# 93_HW_ID.net
KiCad netlist of a schematic drawn in Altium Designer
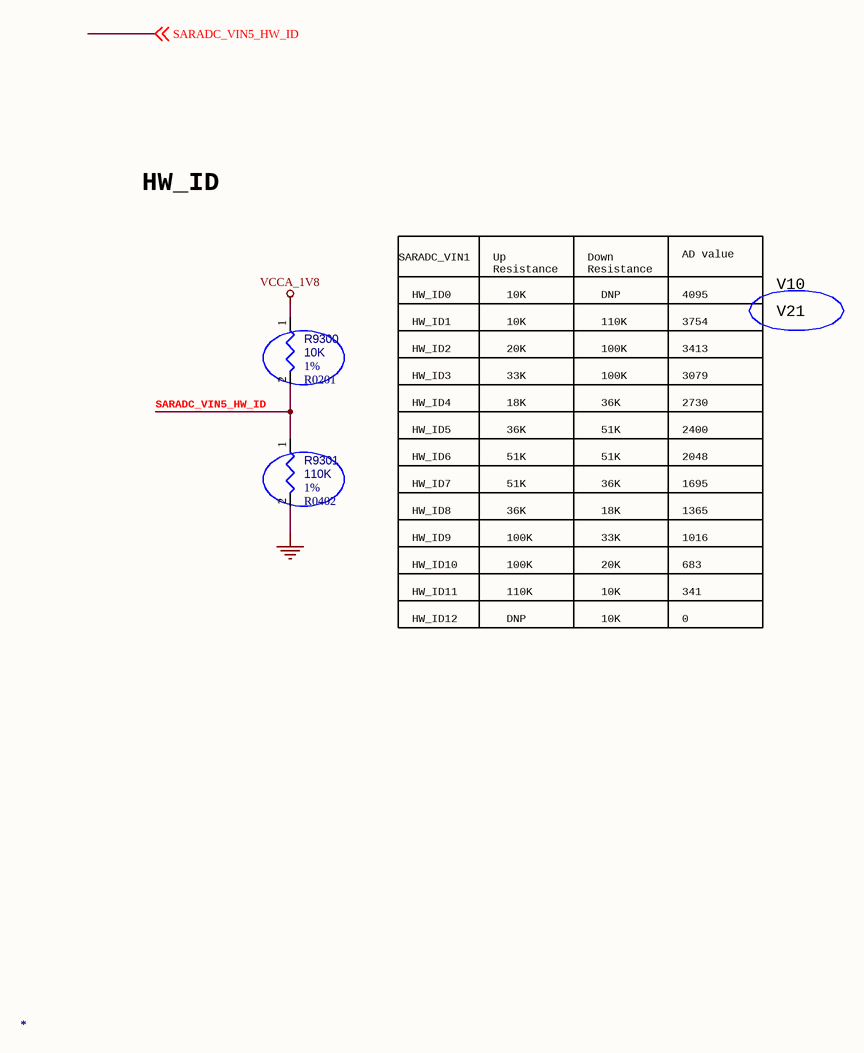
[diagram p0: 93.HW_ID.SchDoc]

(export (version "E")
  (design (tool "Eeschema 10.0.6"))
  (components
    (comp (ref "R9300")
      (value "*")
      (footprint "R0402")
      (description "НЁУГєсД¤µзЧи,10K,+/-1%,R0201,1/20W.")
      (fields
        (field (name "PCB FOOTPRINT") "R0201")
        (field (name "TOLERANCE") "1%")
        (field (name "MANUFACTURER") "YAGEO")
        (field (name "ALTIUM_UNNAMED_1") "10K")
        (field (name "CREATED BY") "YTL")
      )
      (libsource (lib "*") (part "RESISTOR_Dup1"))
    )
    (comp (ref "R9301")
      (value "*")
      (footprint "R0402")
      (description "НЁУГєсД¤µзЧи,110K,+/-1%,R0402,1/16W.")
      (fields
        (field (name "PCB FOOTPRINT") "R0402")
        (field (name "TOLERANCE") "1%")
        (field (name "MANUFACTURER") "YAGEO")
        (field (name "ALTIUM_UNNAMED_1") "110K")
        (field (name "CREATED BY") "YTL")
      )
      (libsource (lib "*") (part "RESISTOR_Dup1"))
    )
  )
  (nets
    (net (code "1") (name "GND") (class "Default")
      (node (ref "R9301") (pin "2") (pinfunction "2_2") (pintype "passive"))
    )
    (net (code "2") (name "SARADC_VIN5_HW_ID") (class "Default")
      (node (ref "R9300") (pin "2") (pinfunction "2_2") (pintype "passive"))
      (node (ref "R9301") (pin "1") (pinfunction "1_1") (pintype "passive"))
    )
    (net (code "3") (name "VCCA_1V8") (class "Default")
      (node (ref "R9300") (pin "1") (pinfunction "1_1") (pintype "passive"))
    )
  )
)
